# dummy-load.net
KiCad netlist of a schematic drawn in EAGLE
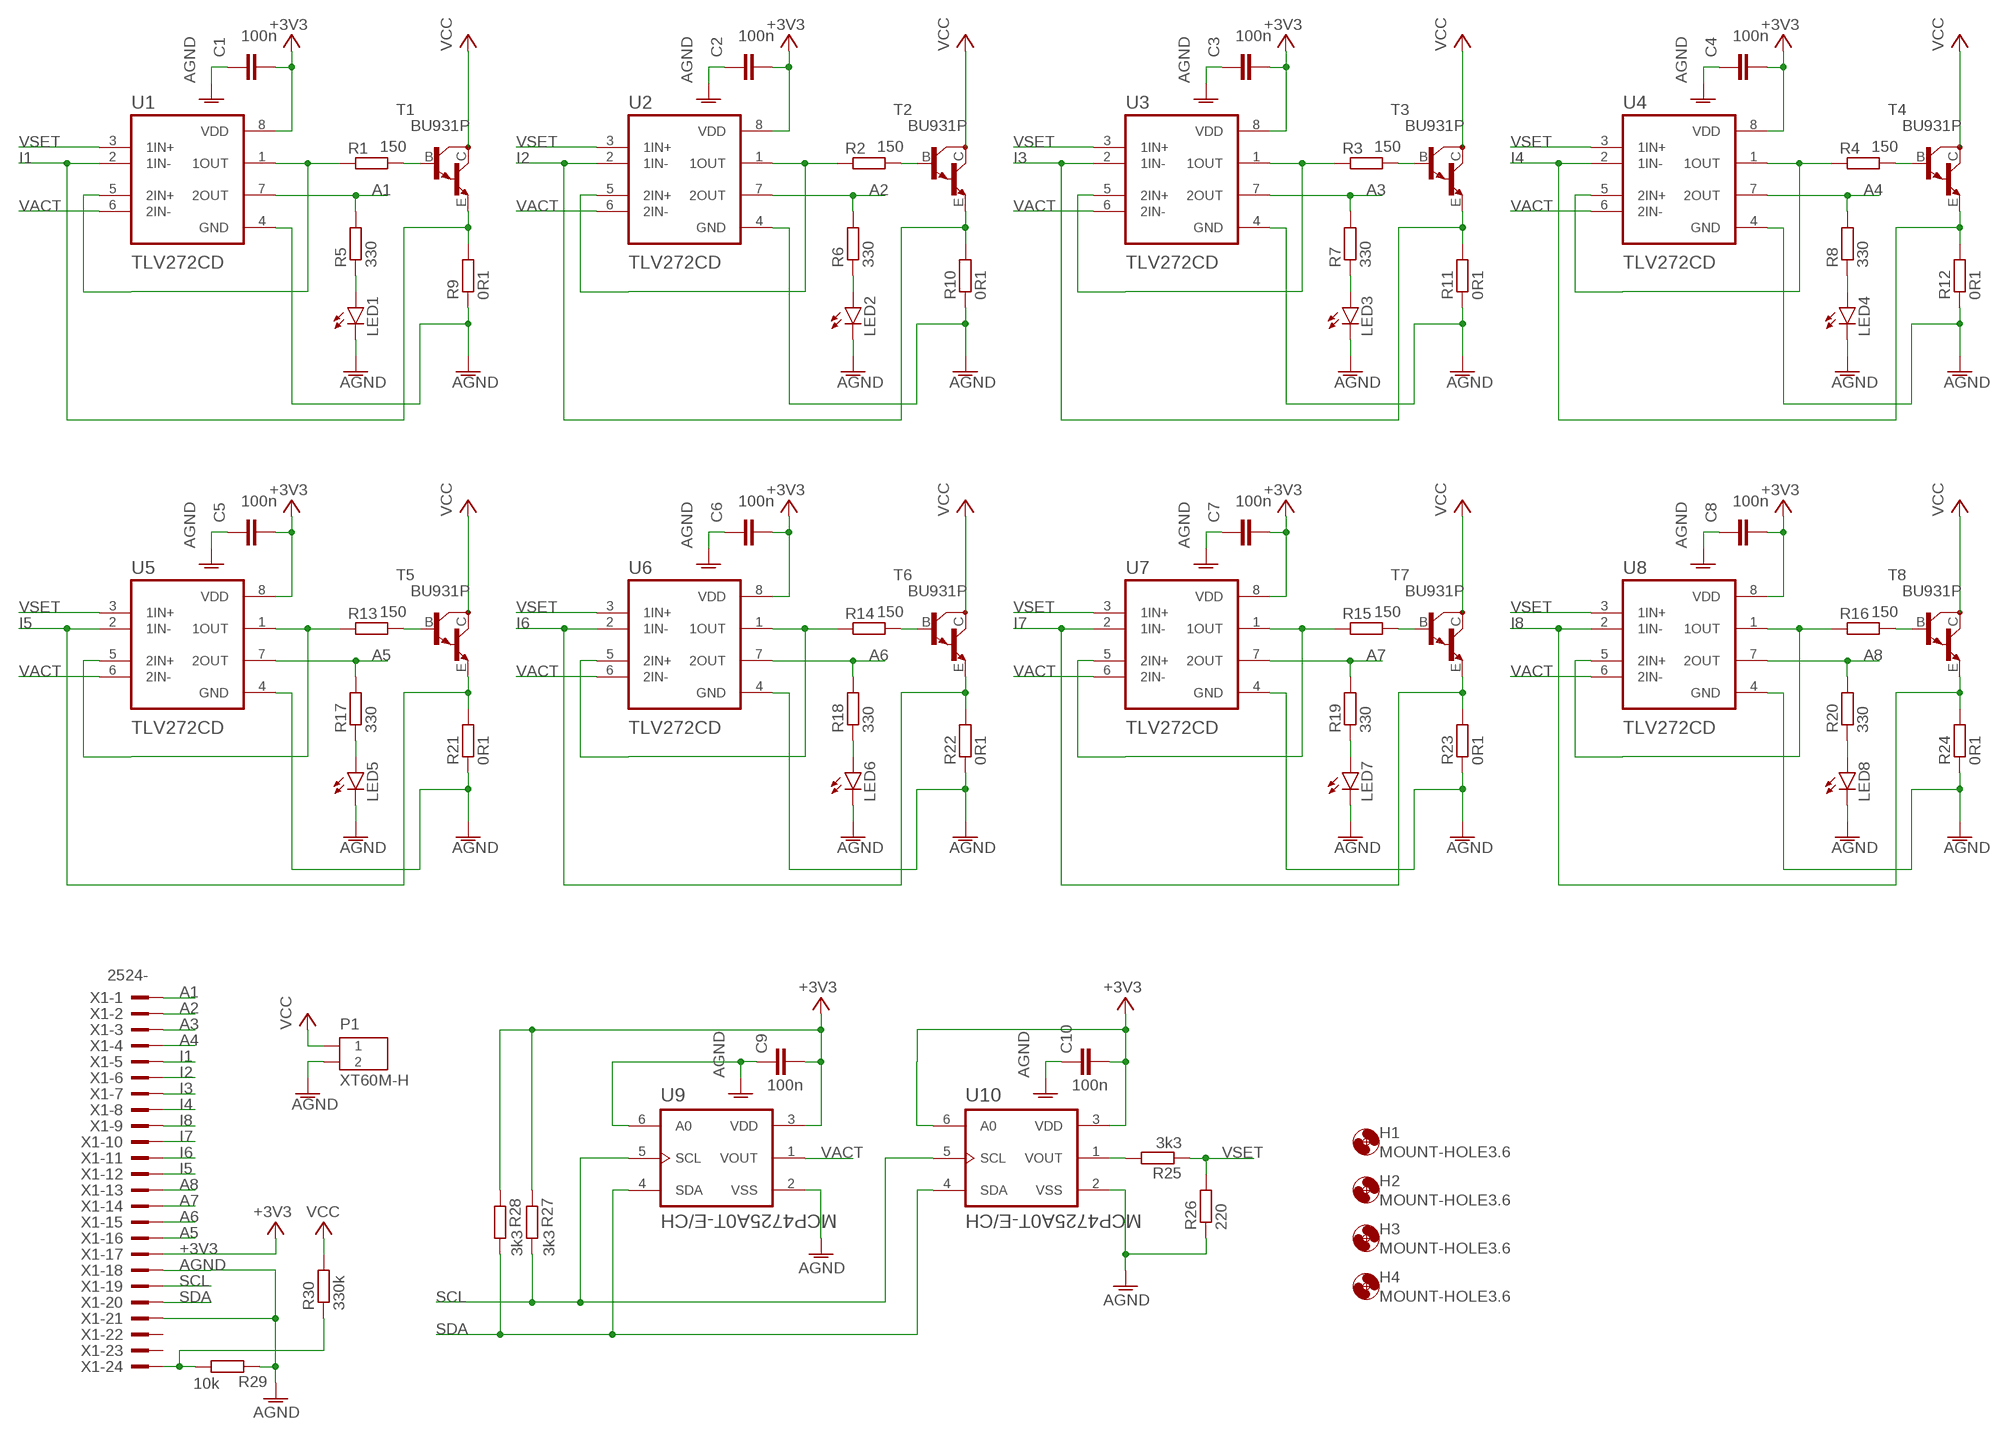
[diagram p0: schematic, sheet 1]

(export (version "E")
  (design (tool "Eeschema 10.0.6"))
  (components
    (comp (ref "C1")
      (value "100n")
      (footprint "eagle-import:C0805")
      (libsource (lib "eagle-import") (part "C-EUC0805"))
    )
    (comp (ref "C2")
      (value "100n")
      (footprint "eagle-import:C0805")
      (libsource (lib "eagle-import") (part "C-EUC0805"))
    )
    (comp (ref "C3")
      (value "100n")
      (footprint "eagle-import:C0805")
      (libsource (lib "eagle-import") (part "C-EUC0805"))
    )
    (comp (ref "C4")
      (value "100n")
      (footprint "eagle-import:C0805")
      (libsource (lib "eagle-import") (part "C-EUC0805"))
    )
    (comp (ref "C5")
      (value "100n")
      (footprint "eagle-import:C0805")
      (libsource (lib "eagle-import") (part "C-EUC0805"))
    )
    (comp (ref "C6")
      (value "100n")
      (footprint "eagle-import:C0805")
      (libsource (lib "eagle-import") (part "C-EUC0805"))
    )
    (comp (ref "C7")
      (value "100n")
      (footprint "eagle-import:C0805")
      (libsource (lib "eagle-import") (part "C-EUC0805"))
    )
    (comp (ref "C8")
      (value "100n")
      (footprint "eagle-import:C0805")
      (libsource (lib "eagle-import") (part "C-EUC0805"))
    )
    (comp (ref "C9")
      (value "100n")
      (footprint "eagle-import:C0805")
      (libsource (lib "eagle-import") (part "C-EUC0805"))
    )
    (comp (ref "C10")
      (value "100n")
      (footprint "eagle-import:C0805")
      (libsource (lib "eagle-import") (part "C-EUC0805"))
    )
    (comp (ref "H1")
      (value "MOUNT-HOLE3.6")
      (footprint "eagle-import:3,6")
      (libsource (lib "eagle-import") (part "MOUNT-HOLE3.6"))
    )
    (comp (ref "H2")
      (value "MOUNT-HOLE3.6")
      (footprint "eagle-import:3,6")
      (libsource (lib "eagle-import") (part "MOUNT-HOLE3.6"))
    )
    (comp (ref "H3")
      (value "MOUNT-HOLE3.6")
      (footprint "eagle-import:3,6")
      (libsource (lib "eagle-import") (part "MOUNT-HOLE3.6"))
    )
    (comp (ref "H4")
      (value "MOUNT-HOLE3.6")
      (footprint "eagle-import:3,6")
      (libsource (lib "eagle-import") (part "MOUNT-HOLE3.6"))
    )
    (comp (ref "LED1")
      (value "LEDCHIP-LED0603")
      (footprint "eagle-import:CHIP-LED0603")
      (libsource (lib "eagle-import") (part "LEDCHIP-LED0603"))
    )
    (comp (ref "LED2")
      (value "LEDCHIP-LED0603")
      (footprint "eagle-import:CHIP-LED0603")
      (libsource (lib "eagle-import") (part "LEDCHIP-LED0603"))
    )
    (comp (ref "LED3")
      (value "LEDCHIP-LED0603")
      (footprint "eagle-import:CHIP-LED0603")
      (libsource (lib "eagle-import") (part "LEDCHIP-LED0603"))
    )
    (comp (ref "LED4")
      (value "LEDCHIP-LED0603")
      (footprint "eagle-import:CHIP-LED0603")
      (libsource (lib "eagle-import") (part "LEDCHIP-LED0603"))
    )
    (comp (ref "LED5")
      (value "LEDCHIP-LED0603")
      (footprint "eagle-import:CHIP-LED0603")
      (libsource (lib "eagle-import") (part "LEDCHIP-LED0603"))
    )
    (comp (ref "LED6")
      (value "LEDCHIP-LED0603")
      (footprint "eagle-import:CHIP-LED0603")
      (libsource (lib "eagle-import") (part "LEDCHIP-LED0603"))
    )
    (comp (ref "LED7")
      (value "LEDCHIP-LED0603")
      (footprint "eagle-import:CHIP-LED0603")
      (libsource (lib "eagle-import") (part "LEDCHIP-LED0603"))
    )
    (comp (ref "LED8")
      (value "LEDCHIP-LED0603")
      (footprint "eagle-import:CHIP-LED0603")
      (libsource (lib "eagle-import") (part "LEDCHIP-LED0603"))
    )
    (comp (ref "P1")
      (value "XT60M-H")
      (footprint "eagle-import:XT60M-H")
      (libsource (lib "eagle-import") (part "XT60M-H"))
    )
    (comp (ref "R1")
      (value "150")
      (footprint "eagle-import:R0805")
      (libsource (lib "eagle-import") (part "R-EU_R0805"))
    )
    (comp (ref "R2")
      (value "150")
      (footprint "eagle-import:R0805")
      (libsource (lib "eagle-import") (part "R-EU_R0805"))
    )
    (comp (ref "R3")
      (value "150")
      (footprint "eagle-import:R0805")
      (libsource (lib "eagle-import") (part "R-EU_R0805"))
    )
    (comp (ref "R4")
      (value "150")
      (footprint "eagle-import:R0805")
      (libsource (lib "eagle-import") (part "R-EU_R0805"))
    )
    (comp (ref "R5")
      (value "330")
      (footprint "eagle-import:R0805")
      (libsource (lib "eagle-import") (part "R-EU_R0805"))
    )
    (comp (ref "R6")
      (value "330")
      (footprint "eagle-import:R0805")
      (libsource (lib "eagle-import") (part "R-EU_R0805"))
    )
    (comp (ref "R7")
      (value "330")
      (footprint "eagle-import:R0805")
      (libsource (lib "eagle-import") (part "R-EU_R0805"))
    )
    (comp (ref "R8")
      (value "330")
      (footprint "eagle-import:R0805")
      (libsource (lib "eagle-import") (part "R-EU_R0805"))
    )
    (comp (ref "R9")
      (value "0R1")
      (footprint "eagle-import:R2512")
      (libsource (lib "eagle-import") (part "R-EU_R2512"))
    )
    (comp (ref "R10")
      (value "0R1")
      (footprint "eagle-import:R2512")
      (libsource (lib "eagle-import") (part "R-EU_R2512"))
    )
    (comp (ref "R11")
      (value "0R1")
      (footprint "eagle-import:R2512")
      (libsource (lib "eagle-import") (part "R-EU_R2512"))
    )
    (comp (ref "R12")
      (value "0R1")
      (footprint "eagle-import:R2512")
      (libsource (lib "eagle-import") (part "R-EU_R2512"))
    )
    (comp (ref "R13")
      (value "150")
      (footprint "eagle-import:R0805")
      (libsource (lib "eagle-import") (part "R-EU_R0805"))
    )
    (comp (ref "R14")
      (value "150")
      (footprint "eagle-import:R0805")
      (libsource (lib "eagle-import") (part "R-EU_R0805"))
    )
    (comp (ref "R15")
      (value "150")
      (footprint "eagle-import:R0805")
      (libsource (lib "eagle-import") (part "R-EU_R0805"))
    )
    (comp (ref "R16")
      (value "150")
      (footprint "eagle-import:R0805")
      (libsource (lib "eagle-import") (part "R-EU_R0805"))
    )
    (comp (ref "R17")
      (value "330")
      (footprint "eagle-import:R0805")
      (libsource (lib "eagle-import") (part "R-EU_R0805"))
    )
    (comp (ref "R18")
      (value "330")
      (footprint "eagle-import:R0805")
      (libsource (lib "eagle-import") (part "R-EU_R0805"))
    )
    (comp (ref "R19")
      (value "330")
      (footprint "eagle-import:R0805")
      (libsource (lib "eagle-import") (part "R-EU_R0805"))
    )
    (comp (ref "R20")
      (value "330")
      (footprint "eagle-import:R0805")
      (libsource (lib "eagle-import") (part "R-EU_R0805"))
    )
    (comp (ref "R21")
      (value "0R1")
      (footprint "eagle-import:R2512")
      (libsource (lib "eagle-import") (part "R-EU_R2512"))
    )
    (comp (ref "R22")
      (value "0R1")
      (footprint "eagle-import:R2512")
      (libsource (lib "eagle-import") (part "R-EU_R2512"))
    )
    (comp (ref "R23")
      (value "0R1")
      (footprint "eagle-import:R2512")
      (libsource (lib "eagle-import") (part "R-EU_R2512"))
    )
    (comp (ref "R24")
      (value "0R1")
      (footprint "eagle-import:R2512")
      (libsource (lib "eagle-import") (part "R-EU_R2512"))
    )
    (comp (ref "R25")
      (value "3k3")
      (footprint "eagle-import:R0805")
      (libsource (lib "eagle-import") (part "R-EU_R0805"))
    )
    (comp (ref "R26")
      (value "220")
      (footprint "eagle-import:R0805")
      (libsource (lib "eagle-import") (part "R-EU_R0805"))
    )
    (comp (ref "R27")
      (value "3k3")
      (footprint "eagle-import:R0805")
      (libsource (lib "eagle-import") (part "R-EU_R0805"))
    )
    (comp (ref "R28")
      (value "3k3")
      (footprint "eagle-import:R0805")
      (libsource (lib "eagle-import") (part "R-EU_R0805"))
    )
    (comp (ref "R29")
      (value "10k")
      (footprint "eagle-import:R0805")
      (libsource (lib "eagle-import") (part "R-EU_R0805"))
    )
    (comp (ref "R30")
      (value "330k")
      (footprint "eagle-import:R0805")
      (libsource (lib "eagle-import") (part "R-EU_R0805"))
    )
    (comp (ref "T1")
      (value "BU931P")
      (footprint "eagle-import:TO-247-H")
      (libsource (lib "eagle-import") (part "BU931P"))
    )
    (comp (ref "T2")
      (value "BU931P")
      (footprint "eagle-import:TO-247-H")
      (libsource (lib "eagle-import") (part "BU931P"))
    )
    (comp (ref "T3")
      (value "BU931P")
      (footprint "eagle-import:TO-247-H")
      (libsource (lib "eagle-import") (part "BU931P"))
    )
    (comp (ref "T4")
      (value "BU931P")
      (footprint "eagle-import:TO-247-H")
      (libsource (lib "eagle-import") (part "BU931P"))
    )
    (comp (ref "T5")
      (value "BU931P")
      (footprint "eagle-import:TO-247-H")
      (libsource (lib "eagle-import") (part "BU931P"))
    )
    (comp (ref "T6")
      (value "BU931P")
      (footprint "eagle-import:TO-247-H")
      (libsource (lib "eagle-import") (part "BU931P"))
    )
    (comp (ref "T7")
      (value "BU931P")
      (footprint "eagle-import:TO-247-H")
      (libsource (lib "eagle-import") (part "BU931P"))
    )
    (comp (ref "T8")
      (value "BU931P")
      (footprint "eagle-import:TO-247-H")
      (libsource (lib "eagle-import") (part "BU931P"))
    )
    (comp (ref "U1")
      (value "TLV272CD")
      (footprint "eagle-import:SOIC127P599X175-8N")
      (fields (field (name "MF") "Texas Instruments"))
      (libsource (lib "eagle-import") (part "TLV272CD"))
    )
    (comp (ref "U2")
      (value "TLV272CD")
      (footprint "eagle-import:SOIC127P599X175-8N")
      (fields (field (name "MF") "Texas Instruments"))
      (libsource (lib "eagle-import") (part "TLV272CD"))
    )
    (comp (ref "U3")
      (value "TLV272CD")
      (footprint "eagle-import:SOIC127P599X175-8N")
      (fields (field (name "MF") "Texas Instruments"))
      (libsource (lib "eagle-import") (part "TLV272CD"))
    )
    (comp (ref "U4")
      (value "TLV272CD")
      (footprint "eagle-import:SOIC127P599X175-8N")
      (fields (field (name "MF") "Texas Instruments"))
      (libsource (lib "eagle-import") (part "TLV272CD"))
    )
    (comp (ref "U5")
      (value "TLV272CD")
      (footprint "eagle-import:SOIC127P599X175-8N")
      (fields (field (name "MF") "Texas Instruments"))
      (libsource (lib "eagle-import") (part "TLV272CD"))
    )
    (comp (ref "U6")
      (value "TLV272CD")
      (footprint "eagle-import:SOIC127P599X175-8N")
      (fields (field (name "MF") "Texas Instruments"))
      (libsource (lib "eagle-import") (part "TLV272CD"))
    )
    (comp (ref "U7")
      (value "TLV272CD")
      (footprint "eagle-import:SOIC127P599X175-8N")
      (fields (field (name "MF") "Texas Instruments"))
      (libsource (lib "eagle-import") (part "TLV272CD"))
    )
    (comp (ref "U8")
      (value "TLV272CD")
      (footprint "eagle-import:SOIC127P599X175-8N")
      (fields (field (name "MF") "Texas Instruments"))
      (libsource (lib "eagle-import") (part "TLV272CD"))
    )
    (comp (ref "U9")
      (value "MCP4725A0T-E/CH")
      (footprint "eagle-import:SOT95P270X145-6N")
      (fields (field (name "MF") "Microchip Technology"))
      (libsource (lib "eagle-import") (part "MCP4725A0T-E/CH"))
    )
    (comp (ref "U10")
      (value "MCP4725A0T-E/CH")
      (footprint "eagle-import:SOT95P270X145-6N")
      (fields (field (name "MF") "Microchip Technology"))
      (libsource (lib "eagle-import") (part "MCP4725A0T-E/CH"))
    )
    (comp (ref "X1")
      (value "2524-")
      (footprint "eagle-import:PAK100_2500-24")
      (libsource (lib "eagle-import") (part "2524-"))
    )
  )
  (nets
    (net (code "1") (name "+3V3") (class "Default")
      (node (ref "C1") (pin "2") (pinfunction "2_2") (pintype "passive"))
      (node (ref "C10") (pin "2") (pinfunction "2_2") (pintype "passive"))
      (node (ref "C2") (pin "2") (pinfunction "2_2") (pintype "passive"))
      (node (ref "C3") (pin "2") (pinfunction "2_2") (pintype "passive"))
      (node (ref "C4") (pin "2") (pinfunction "2_2") (pintype "passive"))
      (node (ref "C5") (pin "2") (pinfunction "2_2") (pintype "passive"))
      (node (ref "C6") (pin "2") (pinfunction "2_2") (pintype "passive"))
      (node (ref "C7") (pin "2") (pinfunction "2_2") (pintype "passive"))
      (node (ref "C8") (pin "2") (pinfunction "2_2") (pintype "passive"))
      (node (ref "C9") (pin "2") (pinfunction "2_2") (pintype "passive"))
      (node (ref "R27") (pin "1") (pinfunction "1_1") (pintype "passive"))
      (node (ref "R28") (pin "1") (pinfunction "1_1") (pintype "passive"))
      (node (ref "U1") (pin "8") (pinfunction "VDD_8") (pintype "power_in"))
      (node (ref "U10") (pin "3") (pinfunction "VDD_3") (pintype "power_in"))
      (node (ref "U10") (pin "6") (pinfunction "A0_6") (pintype "input"))
      (node (ref "U2") (pin "8") (pinfunction "VDD_8") (pintype "power_in"))
      (node (ref "U3") (pin "8") (pinfunction "VDD_8") (pintype "power_in"))
      (node (ref "U4") (pin "8") (pinfunction "VDD_8") (pintype "power_in"))
      (node (ref "U5") (pin "8") (pinfunction "VDD_8") (pintype "power_in"))
      (node (ref "U6") (pin "8") (pinfunction "VDD_8") (pintype "power_in"))
      (node (ref "U7") (pin "8") (pinfunction "VDD_8") (pintype "power_in"))
      (node (ref "U8") (pin "8") (pinfunction "VDD_8") (pintype "power_in"))
      (node (ref "U9") (pin "3") (pinfunction "VDD_3") (pintype "power_in"))
      (node (ref "X1") (pin "17") (pinfunction "KL_17") (pintype "passive"))
    )
    (net (code "2") (name "/A1") (class "Default")
      (node (ref "R5") (pin "2") (pinfunction "2_2") (pintype "passive"))
      (node (ref "U1") (pin "7") (pinfunction "2OUT_7") (pintype "output"))
      (node (ref "X1") (pin "1") (pinfunction "KL_1") (pintype "passive"))
    )
    (net (code "3") (name "/A2") (class "Default")
      (node (ref "R6") (pin "2") (pinfunction "2_2") (pintype "passive"))
      (node (ref "U2") (pin "7") (pinfunction "2OUT_7") (pintype "output"))
      (node (ref "X1") (pin "2") (pinfunction "KL_2") (pintype "passive"))
    )
    (net (code "4") (name "/A3") (class "Default")
      (node (ref "R7") (pin "2") (pinfunction "2_2") (pintype "passive"))
      (node (ref "U3") (pin "7") (pinfunction "2OUT_7") (pintype "output"))
      (node (ref "X1") (pin "3") (pinfunction "KL_3") (pintype "passive"))
    )
    (net (code "5") (name "/A4") (class "Default")
      (node (ref "R8") (pin "2") (pinfunction "2_2") (pintype "passive"))
      (node (ref "U4") (pin "7") (pinfunction "2OUT_7") (pintype "output"))
      (node (ref "X1") (pin "4") (pinfunction "KL_4") (pintype "passive"))
    )
    (net (code "6") (name "/A5") (class "Default")
      (node (ref "R17") (pin "2") (pinfunction "2_2") (pintype "passive"))
      (node (ref "U5") (pin "7") (pinfunction "2OUT_7") (pintype "output"))
      (node (ref "X1") (pin "16") (pinfunction "KL_16") (pintype "passive"))
    )
    (net (code "7") (name "/A6") (class "Default")
      (node (ref "R18") (pin "2") (pinfunction "2_2") (pintype "passive"))
      (node (ref "U6") (pin "7") (pinfunction "2OUT_7") (pintype "output"))
      (node (ref "X1") (pin "15") (pinfunction "KL_15") (pintype "passive"))
    )
    (net (code "8") (name "/A7") (class "Default")
      (node (ref "R19") (pin "2") (pinfunction "2_2") (pintype "passive"))
      (node (ref "U7") (pin "7") (pinfunction "2OUT_7") (pintype "output"))
      (node (ref "X1") (pin "14") (pinfunction "KL_14") (pintype "passive"))
    )
    (net (code "9") (name "/A8") (class "Default")
      (node (ref "R20") (pin "2") (pinfunction "2_2") (pintype "passive"))
      (node (ref "U8") (pin "7") (pinfunction "2OUT_7") (pintype "output"))
      (node (ref "X1") (pin "13") (pinfunction "KL_13") (pintype "passive"))
    )
    (net (code "10") (name "/I1") (class "Default")
      (node (ref "R9") (pin "2") (pinfunction "2_2") (pintype "passive"))
      (node (ref "T1") (pin "E") (pinfunction "E_E") (pintype "passive"))
      (node (ref "U1") (pin "2") (pinfunction "1IN-_2") (pintype "input"))
      (node (ref "X1") (pin "5") (pinfunction "KL_5") (pintype "passive"))
    )
    (net (code "11") (name "/I2") (class "Default")
      (node (ref "R10") (pin "2") (pinfunction "2_2") (pintype "passive"))
      (node (ref "T2") (pin "E") (pinfunction "E_E") (pintype "passive"))
      (node (ref "U2") (pin "2") (pinfunction "1IN-_2") (pintype "input"))
      (node (ref "X1") (pin "6") (pinfunction "KL_6") (pintype "passive"))
    )
    (net (code "12") (name "/I3") (class "Default")
      (node (ref "R11") (pin "2") (pinfunction "2_2") (pintype "passive"))
      (node (ref "T3") (pin "E") (pinfunction "E_E") (pintype "passive"))
      (node (ref "U3") (pin "2") (pinfunction "1IN-_2") (pintype "input"))
      (node (ref "X1") (pin "7") (pinfunction "KL_7") (pintype "passive"))
    )
    (net (code "13") (name "/I4") (class "Default")
      (node (ref "R12") (pin "2") (pinfunction "2_2") (pintype "passive"))
      (node (ref "T4") (pin "E") (pinfunction "E_E") (pintype "passive"))
      (node (ref "U4") (pin "2") (pinfunction "1IN-_2") (pintype "input"))
      (node (ref "X1") (pin "8") (pinfunction "KL_8") (pintype "passive"))
    )
    (net (code "14") (name "/I5") (class "Default")
      (node (ref "R21") (pin "2") (pinfunction "2_2") (pintype "passive"))
      (node (ref "T5") (pin "E") (pinfunction "E_E") (pintype "passive"))
      (node (ref "U5") (pin "2") (pinfunction "1IN-_2") (pintype "input"))
      (node (ref "X1") (pin "12") (pinfunction "KL_12") (pintype "passive"))
    )
    (net (code "15") (name "/I6") (class "Default")
      (node (ref "R22") (pin "2") (pinfunction "2_2") (pintype "passive"))
      (node (ref "T6") (pin "E") (pinfunction "E_E") (pintype "passive"))
      (node (ref "U6") (pin "2") (pinfunction "1IN-_2") (pintype "input"))
      (node (ref "X1") (pin "11") (pinfunction "KL_11") (pintype "passive"))
    )
    (net (code "16") (name "/I7") (class "Default")
      (node (ref "R23") (pin "2") (pinfunction "2_2") (pintype "passive"))
      (node (ref "T7") (pin "E") (pinfunction "E_E") (pintype "passive"))
      (node (ref "U7") (pin "2") (pinfunction "1IN-_2") (pintype "input"))
      (node (ref "X1") (pin "10") (pinfunction "KL_10") (pintype "passive"))
    )
    (net (code "17") (name "/I8") (class "Default")
      (node (ref "R24") (pin "2") (pinfunction "2_2") (pintype "passive"))
      (node (ref "T8") (pin "E") (pinfunction "E_E") (pintype "passive"))
      (node (ref "U8") (pin "2") (pinfunction "1IN-_2") (pintype "input"))
      (node (ref "X1") (pin "9") (pinfunction "KL_9") (pintype "passive"))
    )
    (net (code "18") (name "/SCL") (class "Default")
      (node (ref "R27") (pin "2") (pinfunction "2_2") (pintype "passive"))
      (node (ref "U10") (pin "5") (pinfunction "SCL_5") (pintype "input"))
      (node (ref "U9") (pin "5") (pinfunction "SCL_5") (pintype "input"))
      (node (ref "X1") (pin "19") (pinfunction "KL_19") (pintype "passive"))
    )
    (net (code "19") (name "/SDA") (class "Default")
      (node (ref "R28") (pin "2") (pinfunction "2_2") (pintype "passive"))
      (node (ref "U10") (pin "4") (pinfunction "SDA_4") (pintype "bidirectional"))
      (node (ref "U9") (pin "4") (pinfunction "SDA_4") (pintype "bidirectional"))
      (node (ref "X1") (pin "20") (pinfunction "KL_20") (pintype "passive"))
    )
    (net (code "20") (name "/VACT") (class "Default")
      (node (ref "U1") (pin "6") (pinfunction "2IN-_6") (pintype "input"))
      (node (ref "U2") (pin "6") (pinfunction "2IN-_6") (pintype "input"))
      (node (ref "U3") (pin "6") (pinfunction "2IN-_6") (pintype "input"))
      (node (ref "U4") (pin "6") (pinfunction "2IN-_6") (pintype "input"))
      (node (ref "U5") (pin "6") (pinfunction "2IN-_6") (pintype "input"))
      (node (ref "U6") (pin "6") (pinfunction "2IN-_6") (pintype "input"))
      (node (ref "U7") (pin "6") (pinfunction "2IN-_6") (pintype "input"))
      (node (ref "U8") (pin "6") (pinfunction "2IN-_6") (pintype "input"))
      (node (ref "U9") (pin "1") (pinfunction "VOUT_1") (pintype "output"))
    )
    (net (code "21") (name "/VSET") (class "Default")
      (node (ref "R25") (pin "1") (pinfunction "1_1") (pintype "passive"))
      (node (ref "R26") (pin "2") (pinfunction "2_2") (pintype "passive"))
      (node (ref "U1") (pin "3") (pinfunction "1IN+_3") (pintype "input"))
      (node (ref "U2") (pin "3") (pinfunction "1IN+_3") (pintype "input"))
      (node (ref "U3") (pin "3") (pinfunction "1IN+_3") (pintype "input"))
      (node (ref "U4") (pin "3") (pinfunction "1IN+_3") (pintype "input"))
      (node (ref "U5") (pin "3") (pinfunction "1IN+_3") (pintype "input"))
      (node (ref "U6") (pin "3") (pinfunction "1IN+_3") (pintype "input"))
      (node (ref "U7") (pin "3") (pinfunction "1IN+_3") (pintype "input"))
      (node (ref "U8") (pin "3") (pinfunction "1IN+_3") (pintype "input"))
    )
    (net (code "22") (name "AGND") (class "Default")
      (node (ref "C1") (pin "1") (pinfunction "1_1") (pintype "passive"))
      (node (ref "C10") (pin "1") (pinfunction "1_1") (pintype "passive"))
      (node (ref "C2") (pin "1") (pinfunction "1_1") (pintype "passive"))
      (node (ref "C3") (pin "1") (pinfunction "1_1") (pintype "passive"))
      (node (ref "C4") (pin "1") (pinfunction "1_1") (pintype "passive"))
      (node (ref "C5") (pin "1") (pinfunction "1_1") (pintype "passive"))
      (node (ref "C6") (pin "1") (pinfunction "1_1") (pintype "passive"))
      (node (ref "C7") (pin "1") (pinfunction "1_1") (pintype "passive"))
      (node (ref "C8") (pin "1") (pinfunction "1_1") (pintype "passive"))
      (node (ref "C9") (pin "1") (pinfunction "1_1") (pintype "passive"))
      (node (ref "LED1") (pin "C") (pinfunction "C_C") (pintype "passive"))
      (node (ref "LED2") (pin "C") (pinfunction "C_C") (pintype "passive"))
      (node (ref "LED3") (pin "C") (pinfunction "C_C") (pintype "passive"))
      (node (ref "LED4") (pin "C") (pinfunction "C_C") (pintype "passive"))
      (node (ref "LED5") (pin "C") (pinfunction "C_C") (pintype "passive"))
      (node (ref "LED6") (pin "C") (pinfunction "C_C") (pintype "passive"))
      (node (ref "LED7") (pin "C") (pinfunction "C_C") (pintype "passive"))
      (node (ref "LED8") (pin "C") (pinfunction "C_C") (pintype "passive"))
      (node (ref "P1") (pin "-") (pinfunction "2_-") (pintype "passive"))
      (node (ref "R10") (pin "1") (pinfunction "1_1") (pintype "passive"))
      (node (ref "R11") (pin "1") (pinfunction "1_1") (pintype "passive"))
      (node (ref "R12") (pin "1") (pinfunction "1_1") (pintype "passive"))
      (node (ref "R21") (pin "1") (pinfunction "1_1") (pintype "passive"))
      (node (ref "R22") (pin "1") (pinfunction "1_1") (pintype "passive"))
      (node (ref "R23") (pin "1") (pinfunction "1_1") (pintype "passive"))
      (node (ref "R24") (pin "1") (pinfunction "1_1") (pintype "passive"))
      (node (ref "R26") (pin "1") (pinfunction "1_1") (pintype "passive"))
      (node (ref "R29") (pin "1") (pinfunction "1_1") (pintype "passive"))
      (node (ref "R9") (pin "1") (pinfunction "1_1") (pintype "passive"))
      (node (ref "U1") (pin "4") (pinfunction "GND_4") (pintype "power_in"))
      (node (ref "U10") (pin "2") (pinfunction "VSS_2") (pintype "power_in"))
      (node (ref "U2") (pin "4") (pinfunction "GND_4") (pintype "power_in"))
      (node (ref "U3") (pin "4") (pinfunction "GND_4") (pintype "power_in"))
      (node (ref "U4") (pin "4") (pinfunction "GND_4") (pintype "power_in"))
      (node (ref "U5") (pin "4") (pinfunction "GND_4") (pintype "power_in"))
      (node (ref "U6") (pin "4") (pinfunction "GND_4") (pintype "power_in"))
      (node (ref "U7") (pin "4") (pinfunction "GND_4") (pintype "power_in"))
      (node (ref "U8") (pin "4") (pinfunction "GND_4") (pintype "power_in"))
      (node (ref "U9") (pin "2") (pinfunction "VSS_2") (pintype "power_in"))
      (node (ref "U9") (pin "6") (pinfunction "A0_6") (pintype "input"))
      (node (ref "X1") (pin "18") (pinfunction "KL_18") (pintype "passive"))
      (node (ref "X1") (pin "21") (pinfunction "KL_21") (pintype "passive"))
    )
    (net (code "23") (name "Net-(LED1-PadA)") (class "Default")
      (node (ref "LED1") (pin "A") (pinfunction "A_A") (pintype "passive"))
      (node (ref "R5") (pin "1") (pinfunction "1_1") (pintype "passive"))
    )
    (net (code "24") (name "Net-(LED2-PadA)") (class "Default")
      (node (ref "LED2") (pin "A") (pinfunction "A_A") (pintype "passive"))
      (node (ref "R6") (pin "1") (pinfunction "1_1") (pintype "passive"))
    )
    (net (code "25") (name "Net-(LED3-PadA)") (class "Default")
      (node (ref "LED3") (pin "A") (pinfunction "A_A") (pintype "passive"))
      (node (ref "R7") (pin "1") (pinfunction "1_1") (pintype "passive"))
    )
    (net (code "26") (name "Net-(LED4-PadA)") (class "Default")
      (node (ref "LED4") (pin "A") (pinfunction "A_A") (pintype "passive"))
      (node (ref "R8") (pin "1") (pinfunction "1_1") (pintype "passive"))
    )
    (net (code "27") (name "Net-(LED5-PadA)") (class "Default")
      (node (ref "LED5") (pin "A") (pinfunction "A_A") (pintype "passive"))
      (node (ref "R17") (pin "1") (pinfunction "1_1") (pintype "passive"))
    )
    (net (code "28") (name "Net-(LED6-PadA)") (class "Default")
      (node (ref "LED6") (pin "A") (pinfunction "A_A") (pintype "passive"))
      (node (ref "R18") (pin "1") (pinfunction "1_1") (pintype "passive"))
    )
    (net (code "29") (name "Net-(LED7-PadA)") (class "Default")
      (node (ref "LED7") (pin "A") (pinfunction "A_A") (pintype "passive"))
      (node (ref "R19") (pin "1") (pinfunction "1_1") (pintype "passive"))
    )
    (net (code "30") (name "Net-(LED8-PadA)") (class "Default")
      (node (ref "LED8") (pin "A") (pinfunction "A_A") (pintype "passive"))
      (node (ref "R20") (pin "1") (pinfunction "1_1") (pintype "passive"))
    )
    (net (code "31") (name "Net-(R1-Pad2)") (class "Default")
      (node (ref "R1") (pin "2") (pinfunction "2_2") (pintype "passive"))
      (node (ref "T1") (pin "B") (pinfunction "B_B") (pintype "passive"))
    )
    (net (code "32") (name "Net-(R2-Pad2)") (class "Default")
      (node (ref "R2") (pin "2") (pinfunction "2_2") (pintype "passive"))
      (node (ref "T2") (pin "B") (pinfunction "B_B") (pintype "passive"))
    )
    (net (code "33") (name "Net-(R3-Pad2)") (class "Default")
      (node (ref "R3") (pin "2") (pinfunction "2_2") (pintype "passive"))
      (node (ref "T3") (pin "B") (pinfunction "B_B") (pintype "passive"))
    )
    (net (code "34") (name "Net-(R4-Pad2)") (class "Default")
      (node (ref "R4") (pin "2") (pinfunction "2_2") (pintype "passive"))
      (node (ref "T4") (pin "B") (pinfunction "B_B") (pintype "passive"))
    )
    (net (code "35") (name "Net-(R13-Pad2)") (class "Default")
      (node (ref "R13") (pin "2") (pinfunction "2_2") (pintype "passive"))
      (node (ref "T5") (pin "B") (pinfunction "B_B") (pintype "passive"))
    )
    (net (code "36") (name "Net-(R14-Pad2)") (class "Default")
      (node (ref "R14") (pin "2") (pinfunction "2_2") (pintype "passive"))
      (node (ref "T6") (pin "B") (pinfunction "B_B") (pintype "passive"))
    )
    (net (code "37") (name "Net-(R15-Pad2)") (class "Default")
      (node (ref "R15") (pin "2") (pinfunction "2_2") (pintype "passive"))
      (node (ref "T7") (pin "B") (pinfunction "B_B") (pintype "passive"))
    )
    (net (code "38") (name "Net-(R16-Pad2)") (class "Default")
      (node (ref "R16") (pin "2") (pinfunction "2_2") (pintype "passive"))
      (node (ref "T8") (pin "B") (pinfunction "B_B") (pintype "passive"))
    )
    (net (code "39") (name "Net-(U1-1OUT)") (class "Default")
      (node (ref "R1") (pin "1") (pinfunction "1_1") (pintype "passive"))
      (node (ref "U1") (pin "1") (pinfunction "1OUT_1") (pintype "output"))
      (node (ref "U1") (pin "5") (pinfunction "2IN+_5") (pintype "input"))
    )
    (net (code "40") (name "Net-(U2-1OUT)") (class "Default")
      (node (ref "R2") (pin "1") (pinfunction "1_1") (pintype "passive"))
      (node (ref "U2") (pin "1") (pinfunction "1OUT_1") (pintype "output"))
      (node (ref "U2") (pin "5") (pinfunction "2IN+_5") (pintype "input"))
    )
    (net (code "41") (name "Net-(U3-1OUT)") (class "Default")
      (node (ref "R3") (pin "1") (pinfunction "1_1") (pintype "passive"))
      (node (ref "U3") (pin "1") (pinfunction "1OUT_1") (pintype "output"))
      (node (ref "U3") (pin "5") (pinfunction "2IN+_5") (pintype "input"))
    )
    (net (code "42") (name "Net-(U4-1OUT)") (class "Default")
      (node (ref "R4") (pin "1") (pinfunction "1_1") (pintype "passive"))
      (node (ref "U4") (pin "1") (pinfunction "1OUT_1") (pintype "output"))
      (node (ref "U4") (pin "5") (pinfunction "2IN+_5") (pintype "input"))
    )
    (net (code "43") (name "Net-(U5-1OUT)") (class "Default")
      (node (ref "R13") (pin "1") (pinfunction "1_1") (pintype "passive"))
      (node (ref "U5") (pin "1") (pinfunction "1OUT_1") (pintype "output"))
      (node (ref "U5") (pin "5") (pinfunction "2IN+_5") (pintype "input"))
    )
    (net (code "44") (name "Net-(U6-1OUT)") (class "Default")
      (node (ref "R14") (pin "1") (pinfunction "1_1") (pintype "passive"))
      (node (ref "U6") (pin "1") (pinfunction "1OUT_1") (pintype "output"))
      (node (ref "U6") (pin "5") (pinfunction "2IN+_5") (pintype "input"))
    )
    (net (code "45") (name "Net-(U7-1OUT)") (class "Default")
      (node (ref "R15") (pin "1") (pinfunction "1_1") (pintype "passive"))
      (node (ref "U7") (pin "1") (pinfunction "1OUT_1") (pintype "output"))
      (node (ref "U7") (pin "5") (pinfunction "2IN+_5") (pintype "input"))
    )
    (net (code "46") (name "Net-(U8-1OUT)") (class "Default")
      (node (ref "R16") (pin "1") (pinfunction "1_1") (pintype "passive"))
      (node (ref "U8") (pin "1") (pinfunction "1OUT_1") (pintype "output"))
      (node (ref "U8") (pin "5") (pinfunction "2IN+_5") (pintype "input"))
    )
    (net (code "47") (name "Net-(U10-VOUT)") (class "Default")
      (node (ref "R25") (pin "2") (pinfunction "2_2") (pintype "passive"))
      (node (ref "U10") (pin "1") (pinfunction "VOUT_1") (pintype "output"))
    )
    (net (code "48") (name "Net-(X1Q-KL)") (class "Default")
      (node (ref "R29") (pin "2") (pinfunction "2_2") (pintype "passive"))
      (node (ref "R30") (pin "1") (pinfunction "1_1") (pintype "passive"))
      (node (ref "X1") (pin "24") (pinfunction "KL_24") (pintype "passive"))
    )
    (net (code "49") (name "VCC") (class "Default")
      (node (ref "P1") (pin "+") (pinfunction "1_+") (pintype "passive"))
      (node (ref "R30") (pin "2") (pinfunction "2_2") (pintype "passive"))
      (node (ref "T1") (pin "C") (pinfunction "C_C") (pintype "passive"))
      (node (ref "T2") (pin "C") (pinfunction "C_C") (pintype "passive"))
      (node (ref "T3") (pin "C") (pinfunction "C_C") (pintype "passive"))
      (node (ref "T4") (pin "C") (pinfunction "C_C") (pintype "passive"))
      (node (ref "T5") (pin "C") (pinfunction "C_C") (pintype "passive"))
      (node (ref "T6") (pin "C") (pinfunction "C_C") (pintype "passive"))
      (node (ref "T7") (pin "C") (pinfunction "C_C") (pintype "passive"))
      (node (ref "T8") (pin "C") (pinfunction "C_C") (pintype "passive"))
    )
    (net (code "50") (name "unconnected-(X1O-KL-Pad22)") (class "Default")
      (node (ref "X1") (pin "22") (pinfunction "KL_22") (pintype "passive"))
    )
    (net (code "51") (name "unconnected-(X1P-KL-Pad23)") (class "Default")
      (node (ref "X1") (pin "23") (pinfunction "KL_23") (pintype "passive"))
    )
  )
)
